# SCH_RTC.net
KiCad netlist of a schematic drawn in Altium Designer
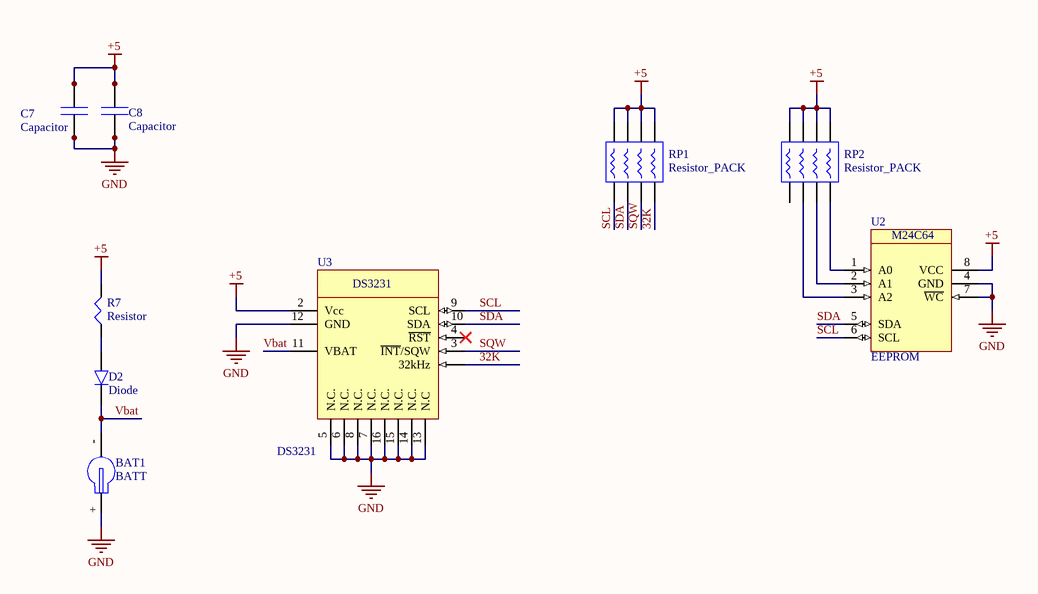
[diagram p0: SCH_RTC.SchDoc]

(export (version "E")
  (design (tool "Eeschema 10.0.6"))
  (components
    (comp (ref "BAT1")
      (value "BATT")
      (description "Porta Pila CR2032")
      (libsource (lib "SCH_LIB") (part "BATT"))
    )
    (comp (ref "C7")
      (value "Capacitor")
      (description "100nF x 50v")
      (libsource (lib "SCH_LIB") (part "Capacitor"))
    )
    (comp (ref "C8")
      (value "Capacitor")
      (description "100nF x 50v")
      (libsource (lib "SCH_LIB") (part "Capacitor"))
    )
    (comp (ref "D2") (value "Diode") (description "Signal Diode") (libsource (lib "SCH_LIB") (part "Diode")))
    (comp (ref "R7") (value "Resistor") (libsource (lib "SCH_LIB") (part "Resistor")))
    (comp (ref "RP1") (value "Resistor_PACK") (libsource (lib "SCH_LIB") (part "Resistor_PACK")))
    (comp (ref "RP2") (value "Resistor_PACK") (libsource (lib "SCH_LIB") (part "Resistor_PACK")))
    (comp (ref "U2") (value "EEPROM") (libsource (lib "SCH_LIB") (part "EEPROM")))
    (comp (ref "U3")
      (value "DS3231")
      (description "Real Time Clock")
      (libsource (lib "SCH_LIB") (part "DS3231"))
    )
  )
  (nets
    (net (code "1") (name "+5") (class "Default")
      (node (ref "C7") (pin "39") (pinfunction "39_39") (pintype "passive"))
      (node (ref "C8") (pin "39") (pinfunction "39_39") (pintype "passive"))
      (node (ref "R7") (pin "48") (pinfunction "48_48") (pintype "passive"))
      (node (ref "RP1") (pin "1") (pinfunction "1_1") (pintype "passive"))
      (node (ref "RP1") (pin "3") (pinfunction "3_3") (pintype "passive"))
      (node (ref "RP1") (pin "5") (pinfunction "5_5") (pintype "passive"))
      (node (ref "RP1") (pin "7") (pinfunction "7_7") (pintype "passive"))
      (node (ref "RP2") (pin "1") (pinfunction "1_1") (pintype "passive"))
      (node (ref "RP2") (pin "3") (pinfunction "3_3") (pintype "passive"))
      (node (ref "RP2") (pin "5") (pinfunction "5_5") (pintype "passive"))
      (node (ref "RP2") (pin "7") (pinfunction "7_7") (pintype "passive"))
      (node (ref "U2") (pin "8") (pinfunction "VCC_8") (pintype "power_in"))
      (node (ref "U3") (pin "2") (pinfunction "Vcc_2") (pintype "power_in"))
    )
    (net (code "2") (name "/32K") (class "Default")
      (node (ref "RP1") (pin "8") (pinfunction "8_8") (pintype "passive"))
      (node (ref "U3") (pin "1") (pinfunction "32kHz_1") (pintype "input"))
    )
    (net (code "3") (name "/SCL") (class "Default")
      (node (ref "RP1") (pin "2") (pinfunction "2_2") (pintype "passive"))
      (node (ref "U2") (pin "6") (pinfunction "SCL_6") (pintype "bidirectional"))
      (node (ref "U3") (pin "9") (pinfunction "SCL_9") (pintype "bidirectional"))
    )
    (net (code "4") (name "/SDA") (class "Default")
      (node (ref "RP1") (pin "4") (pinfunction "4_4") (pintype "passive"))
      (node (ref "U2") (pin "5") (pinfunction "SDA_5") (pintype "bidirectional"))
      (node (ref "U3") (pin "10") (pinfunction "SDA_10") (pintype "bidirectional"))
    )
    (net (code "5") (name "/SQW") (class "Default")
      (node (ref "RP1") (pin "6") (pinfunction "6_6") (pintype "passive"))
      (node (ref "U3") (pin "3") (pinfunction "~{INT}/SQW_3") (pintype "input"))
    )
    (net (code "6") (name "/Vbat") (class "Default")
      (node (ref "BAT1") (pin "-") (pinfunction "2_-") (pintype "passive"))
      (node (ref "D2") (pin "35") (pinfunction "35_35") (pintype "passive"))
      (node (ref "U3") (pin "11") (pinfunction "VBAT_11") (pintype "power_in"))
    )
    (net (code "7") (name "GND") (class "Default")
      (node (ref "BAT1") (pin "+") (pinfunction "1_+") (pintype "passive"))
      (node (ref "C7") (pin "38") (pinfunction "38_38") (pintype "passive"))
      (node (ref "C8") (pin "38") (pinfunction "38_38") (pintype "passive"))
      (node (ref "U2") (pin "4") (pinfunction "GND_4") (pintype "power_in"))
      (node (ref "U2") (pin "7") (pinfunction "~{WC}_7") (pintype "input"))
      (node (ref "U3") (pin "12") (pinfunction "GND_12") (pintype "power_in"))
      (node (ref "U3") (pin "13") (pinfunction "N.C_13") (pintype "passive"))
      (node (ref "U3") (pin "14") (pinfunction "N.C._14") (pintype "passive"))
      (node (ref "U3") (pin "15") (pinfunction "N.C._15") (pintype "passive"))
      (node (ref "U3") (pin "16") (pinfunction "N.C._16") (pintype "passive"))
      (node (ref "U3") (pin "5") (pinfunction "N.C._5") (pintype "passive"))
      (node (ref "U3") (pin "6") (pinfunction "N.C._6") (pintype "passive"))
      (node (ref "U3") (pin "7") (pinfunction "N.C._7") (pintype "passive"))
      (node (ref "U3") (pin "8") (pinfunction "N.C._8") (pintype "passive"))
    )
    (net (code "8") (name "Net-(D2-Pad34)") (class "Default")
      (node (ref "D2") (pin "34") (pinfunction "34_34") (pintype "passive"))
      (node (ref "R7") (pin "47") (pinfunction "47_47") (pintype "passive"))
    )
    (net (code "9") (name "Net-(U2-A0)") (class "Default")
      (node (ref "RP2") (pin "8") (pinfunction "8_8") (pintype "passive"))
      (node (ref "U2") (pin "1") (pinfunction "A0_1") (pintype "input"))
    )
    (net (code "10") (name "Net-(U2-A1)") (class "Default")
      (node (ref "RP2") (pin "6") (pinfunction "6_6") (pintype "passive"))
      (node (ref "U2") (pin "2") (pinfunction "A1_2") (pintype "input"))
    )
    (net (code "11") (name "Net-(U2-A2)") (class "Default")
      (node (ref "RP2") (pin "4") (pinfunction "4_4") (pintype "passive"))
      (node (ref "U2") (pin "3") (pinfunction "A2_3") (pintype "input"))
    )
    (net (code "12") (name "unconnected-(RP2-Pad2)") (class "Default")
      (node (ref "RP2") (pin "2") (pinfunction "2_2") (pintype "passive"))
    )
    (net (code "13") (name "unconnected-(U3-~{RST}-Pad4)") (class "Default")
      (node (ref "U3") (pin "4") (pinfunction "~{RST}_4") (pintype "input+no_connect"))
    )
  )
)
